# ADXL316-module.net
KiCad netlist of a schematic drawn in EAGLE
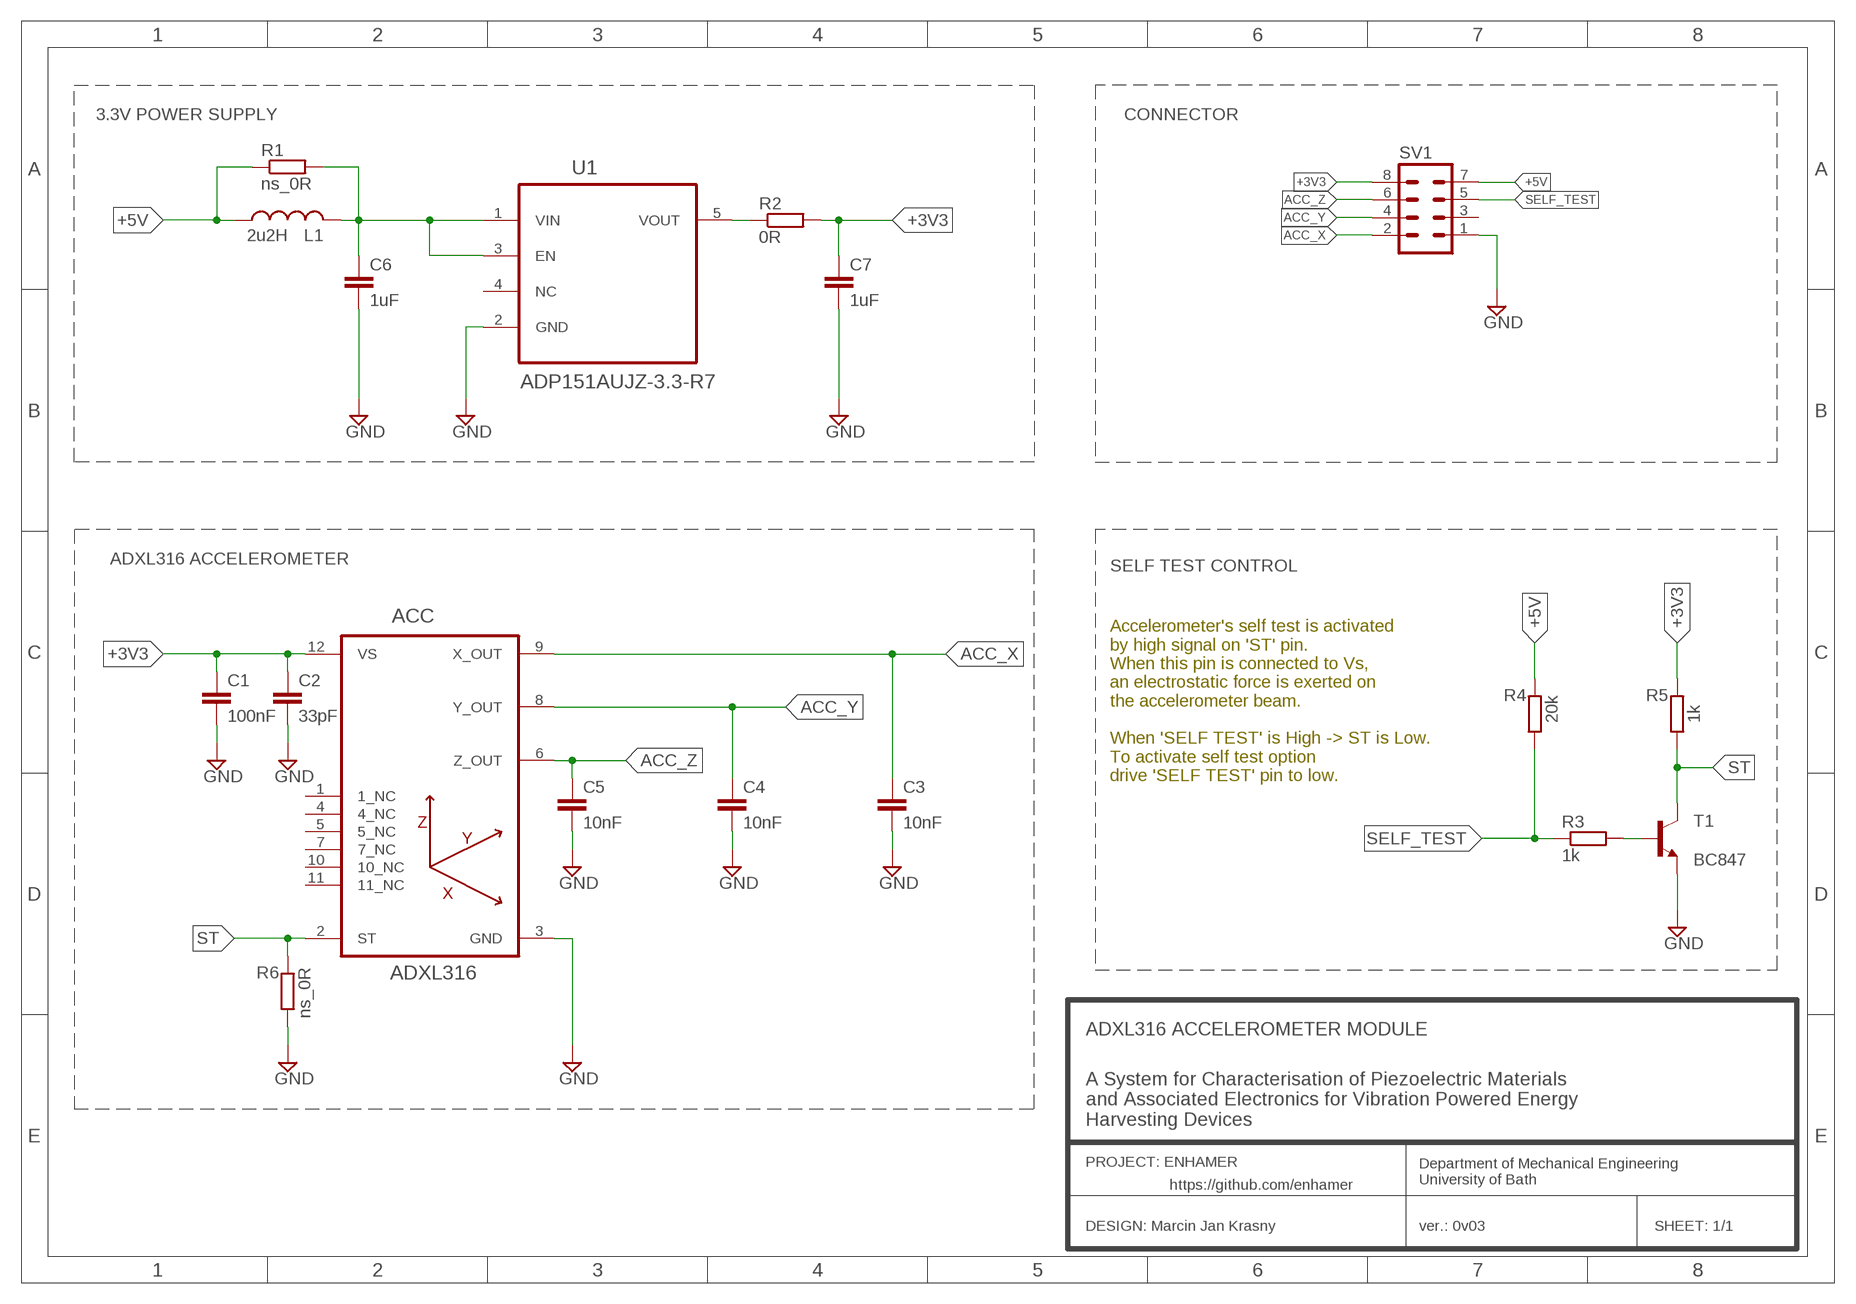
[diagram p0: schematic, sheet 1]

(export (version "E")
  (design (tool "Eeschema 10.0.6"))
  (components
    (comp (ref "ACC")
      (value "ADXL316")
      (footprint "eagle-import:QFN24-4X4_MJK")
      (libsource (lib "eagle-import") (part "ADXL316_MJK"))
    )
    (comp (ref "C1")
      (value "100nF")
      (footprint "eagle-import:0805")
      (libsource (lib "eagle-import") (part "C0805"))
    )
    (comp (ref "C2")
      (value "33pF")
      (footprint "eagle-import:0805")
      (libsource (lib "eagle-import") (part "C0805"))
    )
    (comp (ref "C3")
      (value "10nF")
      (footprint "eagle-import:0805")
      (libsource (lib "eagle-import") (part "C0805"))
    )
    (comp (ref "C4")
      (value "10nF")
      (footprint "eagle-import:0805")
      (libsource (lib "eagle-import") (part "C0805"))
    )
    (comp (ref "C5")
      (value "10nF")
      (footprint "eagle-import:0805")
      (libsource (lib "eagle-import") (part "C0805"))
    )
    (comp (ref "C6")
      (value "1uF")
      (footprint "eagle-import:0805")
      (libsource (lib "eagle-import") (part "C0805"))
    )
    (comp (ref "C7")
      (value "1uF")
      (footprint "eagle-import:0805")
      (libsource (lib "eagle-import") (part "C0805"))
    )
    (comp (ref "L1")
      (value "2u2H")
      (footprint "eagle-import:0805")
      (libsource (lib "eagle-import") (part "L0805_[2016_METRIC]"))
    )
    (comp (ref "R1")
      (value "ns_0R")
      (footprint "eagle-import:0805")
      (libsource (lib "eagle-import") (part "R0805"))
    )
    (comp (ref "R2")
      (value "0R")
      (footprint "eagle-import:0805")
      (libsource (lib "eagle-import") (part "R0805"))
    )
    (comp (ref "R3")
      (value "1k")
      (footprint "eagle-import:0805")
      (libsource (lib "eagle-import") (part "R0805"))
    )
    (comp (ref "R4")
      (value "20k")
      (footprint "eagle-import:0805")
      (libsource (lib "eagle-import") (part "R0805"))
    )
    (comp (ref "R5")
      (value "1k")
      (footprint "eagle-import:0805")
      (libsource (lib "eagle-import") (part "R0805"))
    )
    (comp (ref "R6")
      (value "ns_0R")
      (footprint "eagle-import:0805")
      (libsource (lib "eagle-import") (part "R0805"))
    )
    (comp (ref "SV1")
      (value "MA04-2")
      (footprint "eagle-import:MA04-2")
      (libsource (lib "eagle-import") (part "MA04-2"))
    )
    (comp (ref "T1")
      (value "BC847")
      (footprint "eagle-import:SOT23")
      (libsource (lib "eagle-import") (part "BC847"))
    )
    (comp (ref "U1")
      (value "ADP151AUJZ-3.3-R7")
      (footprint "eagle-import:SOT95P280X100-5N")
      (libsource (lib "eagle-import") (part "ADP151AUJZ-3.3-R7"))
    )
  )
  (nets
    (net (code "1") (name "+3V3") (class "Default")
      (node (ref "ACC") (pin "12") (pinfunction "VS_12") (pintype "bidirectional"))
      (node (ref "C1") (pin "1") (pinfunction "1_1") (pintype "passive"))
      (node (ref "C2") (pin "1") (pinfunction "1_1") (pintype "passive"))
      (node (ref "C7") (pin "1") (pinfunction "1_1") (pintype "passive"))
      (node (ref "R2") (pin "2") (pinfunction "2_2") (pintype "passive"))
      (node (ref "R5") (pin "2") (pinfunction "2_2") (pintype "passive"))
      (node (ref "SV1") (pin "8") (pinfunction "8_8") (pintype "passive"))
    )
    (net (code "2") (name "+5V") (class "Default")
      (node (ref "L1") (pin "1") (pinfunction "1_1") (pintype "passive"))
      (node (ref "R1") (pin "1") (pinfunction "1_1") (pintype "passive"))
      (node (ref "R4") (pin "2") (pinfunction "2_2") (pintype "passive"))
      (node (ref "SV1") (pin "7") (pinfunction "7_7") (pintype "passive"))
    )
    (net (code "3") (name "ACC_X") (class "Default")
      (node (ref "ACC") (pin "9") (pinfunction "X_OUT_9") (pintype "bidirectional"))
      (node (ref "C3") (pin "1") (pinfunction "1_1") (pintype "passive"))
      (node (ref "SV1") (pin "2") (pinfunction "2_2") (pintype "passive"))
    )
    (net (code "4") (name "ACC_Y") (class "Default")
      (node (ref "ACC") (pin "8") (pinfunction "Y_OUT_8") (pintype "bidirectional"))
      (node (ref "C4") (pin "1") (pinfunction "1_1") (pintype "passive"))
      (node (ref "SV1") (pin "4") (pinfunction "4_4") (pintype "passive"))
    )
    (net (code "5") (name "ACC_Z") (class "Default")
      (node (ref "ACC") (pin "6") (pinfunction "Z_OUT_6") (pintype "bidirectional"))
      (node (ref "C5") (pin "1") (pinfunction "1_1") (pintype "passive"))
      (node (ref "SV1") (pin "6") (pinfunction "6_6") (pintype "passive"))
    )
    (net (code "6") (name "GND") (class "Default")
      (node (ref "ACC") (pin "3") (pinfunction "GND_3") (pintype "bidirectional"))
      (node (ref "C1") (pin "2") (pinfunction "2_2") (pintype "passive"))
      (node (ref "C2") (pin "2") (pinfunction "2_2") (pintype "passive"))
      (node (ref "C3") (pin "2") (pinfunction "2_2") (pintype "passive"))
      (node (ref "C4") (pin "2") (pinfunction "2_2") (pintype "passive"))
      (node (ref "C5") (pin "2") (pinfunction "2_2") (pintype "passive"))
      (node (ref "C6") (pin "2") (pinfunction "2_2") (pintype "passive"))
      (node (ref "C7") (pin "2") (pinfunction "2_2") (pintype "passive"))
      (node (ref "R6") (pin "1") (pinfunction "1_1") (pintype "passive"))
      (node (ref "SV1") (pin "1") (pinfunction "1_1") (pintype "passive"))
      (node (ref "T1") (pin "2") (pinfunction "E_2") (pintype "passive"))
      (node (ref "U1") (pin "2") (pinfunction "GND_2") (pintype "passive"))
    )
    (net (code "7") (name "Net-(T1-B)") (class "Default")
      (node (ref "R3") (pin "2") (pinfunction "2_2") (pintype "passive"))
      (node (ref "T1") (pin "1") (pinfunction "B_1") (pintype "passive"))
    )
    (net (code "8") (name "Net-(U1-EN)") (class "Default")
      (node (ref "C6") (pin "1") (pinfunction "1_1") (pintype "passive"))
      (node (ref "L1") (pin "2") (pinfunction "2_2") (pintype "passive"))
      (node (ref "R1") (pin "2") (pinfunction "2_2") (pintype "passive"))
      (node (ref "U1") (pin "1") (pinfunction "VIN_1") (pintype "power_in"))
      (node (ref "U1") (pin "3") (pinfunction "EN_3") (pintype "input"))
    )
    (net (code "9") (name "Net-(U1-VOUT)") (class "Default")
      (node (ref "R2") (pin "1") (pinfunction "1_1") (pintype "passive"))
      (node (ref "U1") (pin "5") (pinfunction "VOUT_5") (pintype "output"))
    )
    (net (code "10") (name "SELF_TEST") (class "Default")
      (node (ref "R3") (pin "1") (pinfunction "1_1") (pintype "passive"))
      (node (ref "R4") (pin "1") (pinfunction "1_1") (pintype "passive"))
      (node (ref "SV1") (pin "5") (pinfunction "5_5") (pintype "passive"))
    )
    (net (code "11") (name "ST") (class "Default")
      (node (ref "ACC") (pin "2") (pinfunction "ST_2") (pintype "bidirectional"))
      (node (ref "R5") (pin "1") (pinfunction "1_1") (pintype "passive"))
      (node (ref "R6") (pin "2") (pinfunction "2_2") (pintype "passive"))
      (node (ref "T1") (pin "3") (pinfunction "C_3") (pintype "passive"))
    )
    (net (code "12") (name "unconnected-(ACC-1_NC-Pad1)") (class "Default")
      (node (ref "ACC") (pin "1") (pinfunction "1_NC_1") (pintype "bidirectional"))
    )
    (net (code "13") (name "unconnected-(ACC-4_NC-Pad4)") (class "Default")
      (node (ref "ACC") (pin "4") (pinfunction "4_NC_4") (pintype "bidirectional"))
    )
    (net (code "14") (name "unconnected-(ACC-5_NC-Pad5)") (class "Default")
      (node (ref "ACC") (pin "5") (pinfunction "5_NC_5") (pintype "bidirectional"))
    )
    (net (code "15") (name "unconnected-(ACC-7_NC-Pad7)") (class "Default")
      (node (ref "ACC") (pin "7") (pinfunction "7_NC_7") (pintype "bidirectional"))
    )
    (net (code "16") (name "unconnected-(ACC-10_NC-Pad10)") (class "Default")
      (node (ref "ACC") (pin "10") (pinfunction "10_NC_10") (pintype "bidirectional"))
    )
    (net (code "17") (name "unconnected-(ACC-11_NC-Pad11)") (class "Default")
      (node (ref "ACC") (pin "11") (pinfunction "11_NC_11") (pintype "bidirectional"))
    )
    (net (code "18") (name "unconnected-(SV1-Pad3)") (class "Default")
      (node (ref "SV1") (pin "3") (pinfunction "3_3") (pintype "passive"))
    )
    (net (code "19") (name "unconnected-(U1-NC-Pad4)") (class "Default")
      (node (ref "U1") (pin "4") (pinfunction "NC_4") (pintype "no_connect"))
    )
  )
)
